# Test_board.net
KiCad netlist of a schematic drawn in EAGLE
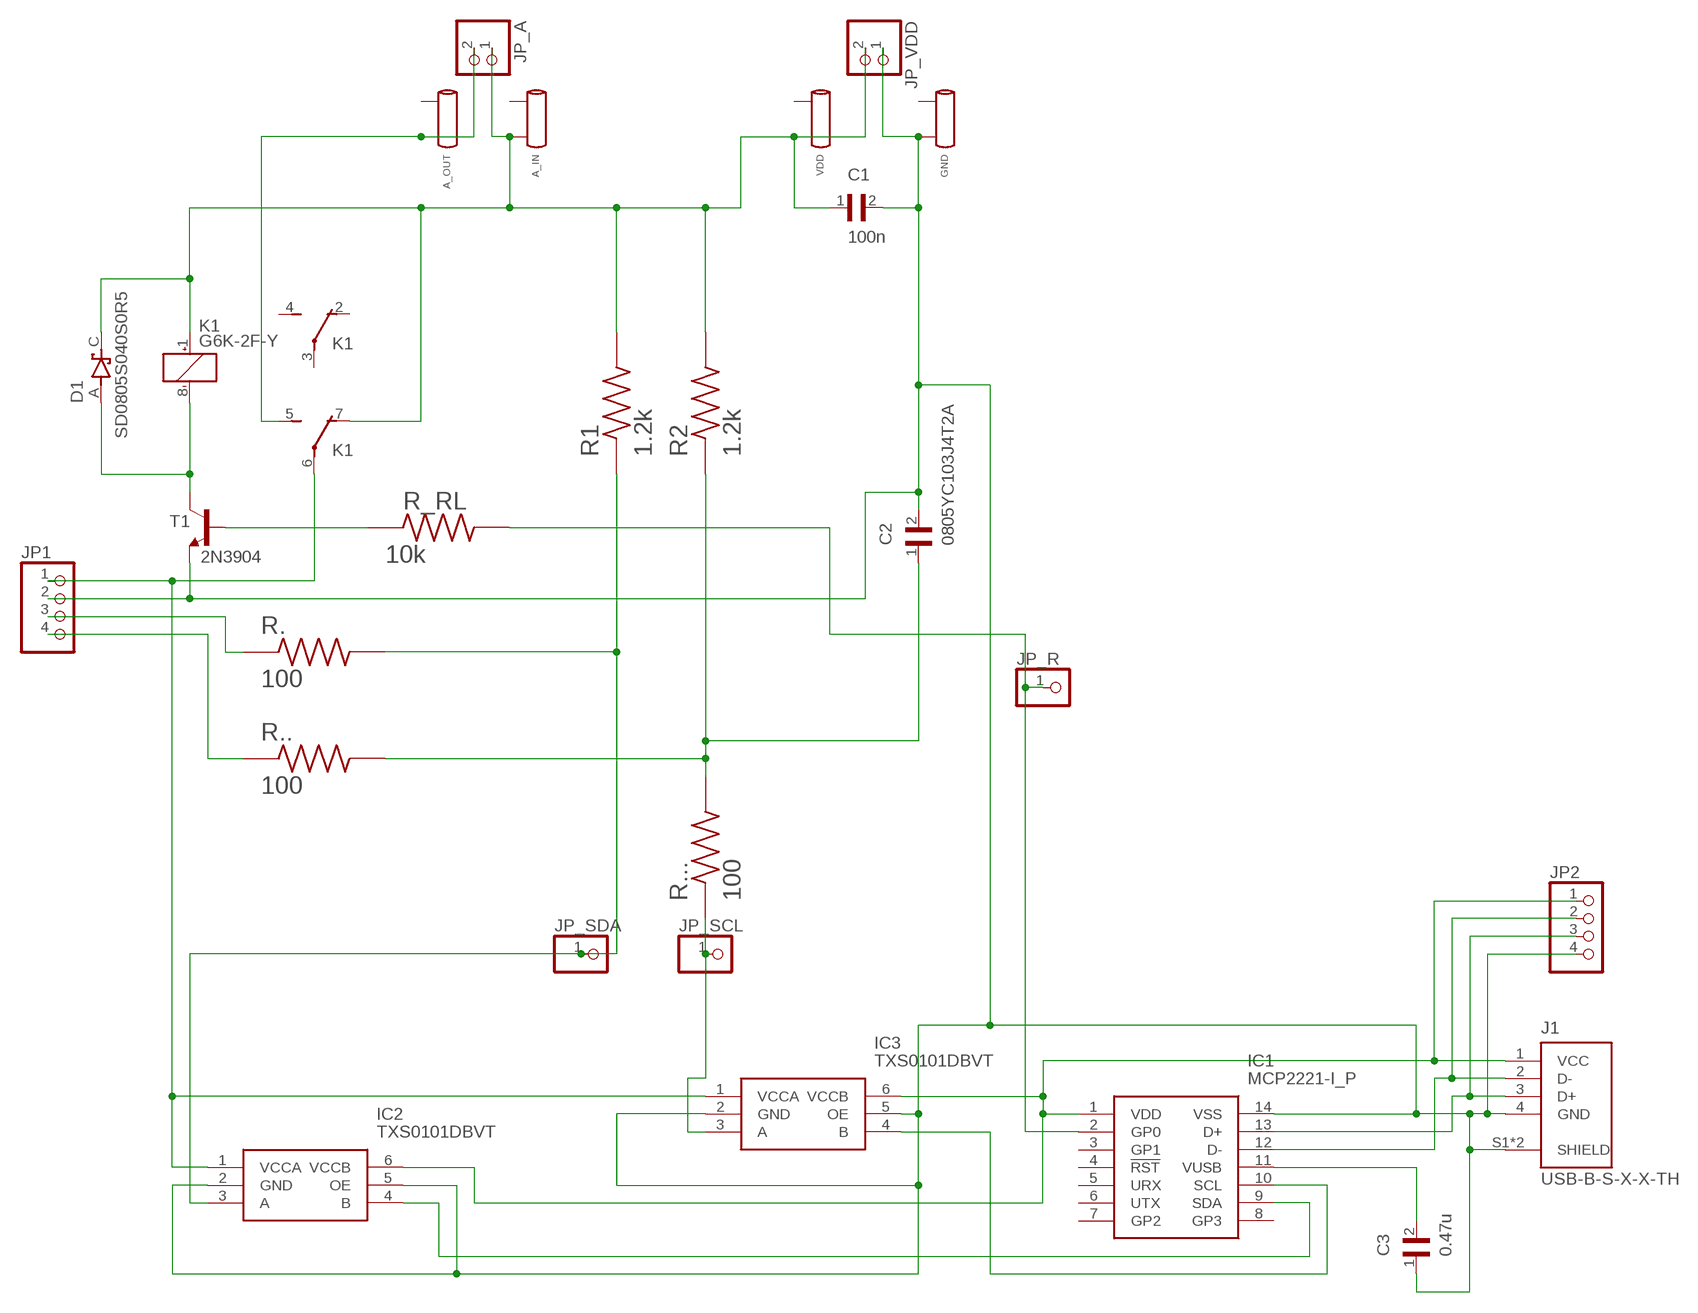
[diagram p0: schematic, sheet 1]

(export (version "E")
  (design (tool "Eeschema 10.0.6"))
  (components
    (comp (ref "A_IN")
      (value "FY_TESTSOCKET")
      (footprint "eagle-import:FY_TESTSOCKET")
      (libsource (lib "eagle-import") (part "FY_TESTSOCKET"))
    )
    (comp (ref "A_OUT")
      (value "FY_TESTSOCKET")
      (footprint "eagle-import:FY_TESTSOCKET")
      (libsource (lib "eagle-import") (part "FY_TESTSOCKET"))
    )
    (comp (ref "C1")
      (value "100n")
      (footprint "eagle-import:CAPC2012X94N")
      (fields (field (name "MF") "AVX") (field (name "MP") "0805YC103J4T2A"))
      (libsource (lib "eagle-import") (part "0805YC103J4T2A"))
    )
    (comp (ref "C2")
      (value "0805YC103J4T2A")
      (footprint "eagle-import:CAPC2012X94N")
      (fields (field (name "MF") "AVX"))
      (libsource (lib "eagle-import") (part "0805YC103J4T2A"))
    )
    (comp (ref "C3")
      (value "0.47u")
      (footprint "eagle-import:CAPC2012X94N")
      (fields (field (name "MF") "AVX") (field (name "MP") "0805YC103J4T2A"))
      (libsource (lib "eagle-import") (part "0805YC103J4T2A"))
    )
    (comp (ref "D1")
      (value "SD0805S040S0R5")
      (footprint "eagle-import:DIOSC130X200X100-2N")
      (fields (field (name "MF") "AVX"))
      (libsource (lib "eagle-import") (part "SD0805S040S0R5"))
    )
    (comp (ref "GND")
      (value "FY_TESTSOCKET")
      (footprint "eagle-import:FY_TESTSOCKET")
      (libsource (lib "eagle-import") (part "FY_TESTSOCKET"))
    )
    (comp (ref "IC1")
      (value "MCP2221-I_P")
      (footprint "eagle-import:DIP781W56P254L1918H533Q14N")
      (fields
        (field (name "ARROW_PART_NUMBER") "MCP2221-I/P")
        (field (name "MOUSER_PART_NUMBER") "579-MCP2221-I/P")
      )
      (libsource (lib "eagle-import") (part "MCP2221-I_P"))
    )
    (comp (ref "IC2")
      (value "TXS0101DBVT")
      (footprint "eagle-import:SOT95P280X145-6N")
      (fields (field (name "MOUSER_PART_NUMBER") "595-TXS0101DBVT"))
      (libsource (lib "eagle-import") (part "TXS0101DBVT"))
    )
    (comp (ref "IC3")
      (value "TXS0101DBVT")
      (footprint "eagle-import:SOT95P280X145-6N")
      (fields (field (name "MOUSER_PART_NUMBER") "595-TXS0101DBVT"))
      (libsource (lib "eagle-import") (part "TXS0101DBVT"))
    )
    (comp (ref "J1")
      (value "USB-B-S-X-X-TH")
      (footprint "eagle-import:SAMTEC_USB-B-S-X-X-TH")
      (fields (field (name "MF") "Samtec") (field (name "MP") "USB-B-S-F-B-TH"))
      (libsource (lib "eagle-import") (part "USB-B-S-X-X-TH"))
    )
    (comp (ref "JP1")
      (value "PINHD-1X4")
      (footprint "eagle-import:1X04")
      (libsource (lib "eagle-import") (part "PINHD-1X4"))
    )
    (comp (ref "JP2")
      (value "PINHD-1X4")
      (footprint "eagle-import:1X04")
      (libsource (lib "eagle-import") (part "PINHD-1X4"))
    )
    (comp (ref "JP_A")
      (value "PINHD-1X2")
      (footprint "eagle-import:1X02")
      (libsource (lib "eagle-import") (part "PINHD-1X2"))
    )
    (comp (ref "JP_R")
      (value "PINHD-1X1")
      (footprint "eagle-import:1X01")
      (libsource (lib "eagle-import") (part "PINHD-1X1"))
    )
    (comp (ref "JP_SCL")
      (value "PINHD-1X1")
      (footprint "eagle-import:1X01")
      (libsource (lib "eagle-import") (part "PINHD-1X1"))
    )
    (comp (ref "JP_SDA")
      (value "PINHD-1X1")
      (footprint "eagle-import:1X01")
      (libsource (lib "eagle-import") (part "PINHD-1X1"))
    )
    (comp (ref "JP_VDD")
      (value "PINHD-1X2")
      (footprint "eagle-import:1X02")
      (libsource (lib "eagle-import") (part "PINHD-1X2"))
    )
    (comp (ref "K1")
      (value "G6K-2F-Y")
      (footprint "eagle-import:G6K-2F-Y")
      (fields (field (name "MF") "OMRON COMPONENTS USA") (field (name "MPN") "G6K-2F-Y DC3"))
      (libsource (lib "eagle-import") (part "G6K-2F-Y"))
    )
    (comp (ref "R.")
      (value "100")
      (footprint "eagle-import:RESC2012X60N")
      (fields (field (name "MF") "Bourns") (field (name "MP") "CR0805AJ/-000EAS"))
      (libsource (lib "eagle-import") (part "CR0805AJ/-000EAS"))
    )
    (comp (ref "R..")
      (value "100")
      (footprint "eagle-import:RESC2012X60N")
      (fields (field (name "MF") "Bourns") (field (name "MP") "CR0805AJ/-000EAS"))
      (libsource (lib "eagle-import") (part "CR0805AJ/-000EAS"))
    )
    (comp (ref "R...")
      (value "100")
      (footprint "eagle-import:RESC2012X60N")
      (fields (field (name "MF") "Bourns") (field (name "MP") "CR0805AJ/-000EAS"))
      (libsource (lib "eagle-import") (part "CR0805AJ/-000EAS"))
    )
    (comp (ref "R1")
      (value "1.2k")
      (footprint "eagle-import:RESC2012X60N")
      (fields (field (name "MF") "Bourns") (field (name "MP") "CR0805AJ/-000EAS"))
      (libsource (lib "eagle-import") (part "CR0805AJ/-000EAS"))
    )
    (comp (ref "R2")
      (value "1.2k")
      (footprint "eagle-import:RESC2012X60N")
      (fields (field (name "MF") "Bourns") (field (name "MP") "CR0805AJ/-000EAS"))
      (libsource (lib "eagle-import") (part "CR0805AJ/-000EAS"))
    )
    (comp (ref "R_RL")
      (value "10k")
      (footprint "eagle-import:RESC2012X60N")
      (fields (field (name "MF") "Bourns") (field (name "MP") "CR0805AJ/-000EAS"))
      (libsource (lib "eagle-import") (part "CR0805AJ/-000EAS"))
    )
    (comp (ref "T1")
      (value "2N3904")
      (footprint "eagle-import:TO92")
      (libsource (lib "eagle-import") (part "2N3904"))
    )
    (comp (ref "VDD")
      (value "FY_TESTSOCKET")
      (footprint "eagle-import:FY_TESTSOCKET")
      (libsource (lib "eagle-import") (part "FY_TESTSOCKET"))
    )
  )
  (nets
    (net (code "1") (name "Net-(C2-Pad1)") (class "Default")
      (node (ref "C2") (pin "1") (pinfunction "1_1") (pintype "passive"))
      (node (ref "R..") (pin "2") (pinfunction "2_2") (pintype "passive"))
      (node (ref "R...") (pin "2") (pinfunction "2_2") (pintype "passive"))
      (node (ref "R2") (pin "1") (pinfunction "1_1") (pintype "passive"))
    )
    (net (code "2") (name "Net-(D1-K)") (class "Default")
      (node (ref "A_IN") (pin "P$2") (pinfunction "P$2_P$2") (pintype "bidirectional"))
      (node (ref "C1") (pin "1") (pinfunction "1_1") (pintype "passive"))
      (node (ref "D1") (pin "C") (pinfunction "K_C") (pintype "passive"))
      (node (ref "JP_A") (pin "1") (pinfunction "1_1") (pintype "passive"))
      (node (ref "JP_VDD") (pin "2") (pinfunction "2_2") (pintype "passive"))
      (node (ref "K1") (pin "1") (pinfunction "+_1") (pintype "passive"))
      (node (ref "K1") (pin "7") (pinfunction "O_7") (pintype "passive"))
      (node (ref "R1") (pin "2") (pinfunction "2_2") (pintype "passive"))
      (node (ref "R2") (pin "2") (pinfunction "2_2") (pintype "passive"))
      (node (ref "VDD") (pin "P$2") (pinfunction "P$2_P$2") (pintype "bidirectional"))
    )
    (net (code "3") (name "Net-(IC1-D+)") (class "Default")
      (node (ref "IC1") (pin "13") (pinfunction "D+_13") (pintype "bidirectional"))
      (node (ref "J1") (pin "3") (pinfunction "D+_3") (pintype "bidirectional"))
      (node (ref "JP2") (pin "3") (pinfunction "3_3") (pintype "passive"))
    )
    (net (code "4") (name "Net-(IC1-D-)") (class "Default")
      (node (ref "IC1") (pin "12") (pinfunction "D-_12") (pintype "bidirectional"))
      (node (ref "J1") (pin "2") (pinfunction "D-_2") (pintype "bidirectional"))
      (node (ref "JP2") (pin "2") (pinfunction "2_2") (pintype "passive"))
    )
    (net (code "5") (name "Net-(IC1-GP0)") (class "Default")
      (node (ref "IC1") (pin "2") (pinfunction "GP0_2") (pintype "bidirectional"))
      (node (ref "JP_R") (pin "1") (pinfunction "1_1") (pintype "passive"))
      (node (ref "R_RL") (pin "2") (pinfunction "2_2") (pintype "passive"))
    )
    (net (code "6") (name "Net-(IC1-SCL)") (class "Default")
      (node (ref "IC1") (pin "10") (pinfunction "SCL_10") (pintype "bidirectional"))
      (node (ref "IC3") (pin "4") (pinfunction "B_4") (pintype "bidirectional"))
    )
    (net (code "7") (name "Net-(IC1-SDA)") (class "Default")
      (node (ref "IC1") (pin "9") (pinfunction "SDA_9") (pintype "bidirectional"))
      (node (ref "IC2") (pin "4") (pinfunction "B_4") (pintype "bidirectional"))
    )
    (net (code "8") (name "Net-(IC1-VDD)") (class "Default")
      (node (ref "IC1") (pin "1") (pinfunction "VDD_1") (pintype "bidirectional"))
      (node (ref "IC2") (pin "6") (pinfunction "VCCB_6") (pintype "bidirectional"))
      (node (ref "IC3") (pin "6") (pinfunction "VCCB_6") (pintype "bidirectional"))
      (node (ref "J1") (pin "1") (pinfunction "VCC_1") (pintype "power_in"))
      (node (ref "JP2") (pin "1") (pinfunction "1_1") (pintype "passive"))
    )
    (net (code "9") (name "Net-(IC1-VSS)") (class "Default")
      (node (ref "C1") (pin "2") (pinfunction "2_2") (pintype "passive"))
      (node (ref "C2") (pin "2") (pinfunction "2_2") (pintype "passive"))
      (node (ref "C3") (pin "1") (pinfunction "1_1") (pintype "passive"))
      (node (ref "GND") (pin "P$2") (pinfunction "P$2_P$2") (pintype "bidirectional"))
      (node (ref "IC1") (pin "14") (pinfunction "VSS_14") (pintype "bidirectional"))
      (node (ref "IC2") (pin "2") (pinfunction "GND_2") (pintype "bidirectional"))
      (node (ref "IC2") (pin "5") (pinfunction "OE_5") (pintype "bidirectional"))
      (node (ref "IC3") (pin "2") (pinfunction "GND_2") (pintype "bidirectional"))
      (node (ref "IC3") (pin "5") (pinfunction "OE_5") (pintype "bidirectional"))
      (node (ref "J1") (pin "4") (pinfunction "GND_4") (pintype "power_in"))
      (node (ref "J1") (pin "S1") (pinfunction "SHIELD_S1") (pintype "passive"))
      (node (ref "J1") (pin "S2") (pinfunction "SHIELD_S2") (pintype "passive"))
      (node (ref "JP1") (pin "2") (pinfunction "2_2") (pintype "passive"))
      (node (ref "JP2") (pin "4") (pinfunction "4_4") (pintype "passive"))
      (node (ref "JP_VDD") (pin "1") (pinfunction "1_1") (pintype "passive"))
      (node (ref "T1") (pin "3") (pinfunction "E_3") (pintype "passive"))
    )
    (net (code "10") (name "Net-(IC1-VUSB)") (class "Default")
      (node (ref "C3") (pin "2") (pinfunction "2_2") (pintype "passive"))
      (node (ref "IC1") (pin "11") (pinfunction "VUSB_11") (pintype "bidirectional"))
    )
    (net (code "11") (name "Net-(IC2-A)") (class "Default")
      (node (ref "IC2") (pin "3") (pinfunction "A_3") (pintype "bidirectional"))
      (node (ref "JP_SDA") (pin "1") (pinfunction "1_1") (pintype "passive"))
      (node (ref "R.") (pin "2") (pinfunction "2_2") (pintype "passive"))
      (node (ref "R1") (pin "1") (pinfunction "1_1") (pintype "passive"))
    )
    (net (code "12") (name "Net-(IC2-VCCA)") (class "Default")
      (node (ref "IC2") (pin "1") (pinfunction "VCCA_1") (pintype "bidirectional"))
      (node (ref "IC3") (pin "1") (pinfunction "VCCA_1") (pintype "bidirectional"))
      (node (ref "JP1") (pin "1") (pinfunction "1_1") (pintype "passive"))
      (node (ref "K1") (pin "6") (pinfunction "P_6") (pintype "passive"))
    )
    (net (code "13") (name "Net-(IC3-A)") (class "Default")
      (node (ref "IC3") (pin "3") (pinfunction "A_3") (pintype "bidirectional"))
      (node (ref "JP_SCL") (pin "1") (pinfunction "1_1") (pintype "passive"))
      (node (ref "R...") (pin "1") (pinfunction "1_1") (pintype "passive"))
    )
    (net (code "14") (name "Net-(JP1-Pad3)") (class "Default")
      (node (ref "JP1") (pin "3") (pinfunction "3_3") (pintype "passive"))
      (node (ref "R.") (pin "1") (pinfunction "1_1") (pintype "passive"))
    )
    (net (code "15") (name "Net-(JP1-Pad4)") (class "Default")
      (node (ref "JP1") (pin "4") (pinfunction "4_4") (pintype "passive"))
      (node (ref "R..") (pin "1") (pinfunction "1_1") (pintype "passive"))
    )
    (net (code "16") (name "Net-(K1A--)") (class "Default")
      (node (ref "D1") (pin "A") (pinfunction "A_A") (pintype "passive"))
      (node (ref "K1") (pin "8") (pinfunction "-_8") (pintype "passive"))
      (node (ref "T1") (pin "1") (pinfunction "C_1") (pintype "passive"))
    )
    (net (code "17") (name "Net-(K1C-S)") (class "Default")
      (node (ref "A_OUT") (pin "P$2") (pinfunction "P$2_P$2") (pintype "bidirectional"))
      (node (ref "JP_A") (pin "2") (pinfunction "2_2") (pintype "passive"))
      (node (ref "K1") (pin "5") (pinfunction "S_5") (pintype "passive"))
    )
    (net (code "18") (name "Net-(T1-B)") (class "Default")
      (node (ref "R_RL") (pin "1") (pinfunction "1_1") (pintype "passive"))
      (node (ref "T1") (pin "2") (pinfunction "B_2") (pintype "passive"))
    )
    (net (code "19") (name "unconnected-(A_IN-PadP$1)") (class "Default")
      (node (ref "A_IN") (pin "P$1") (pinfunction "P$1_P$1") (pintype "bidirectional"))
    )
    (net (code "20") (name "unconnected-(A_OUT-PadP$1)") (class "Default")
      (node (ref "A_OUT") (pin "P$1") (pinfunction "P$1_P$1") (pintype "bidirectional"))
    )
    (net (code "21") (name "unconnected-(GND-PadP$1)") (class "Default")
      (node (ref "GND") (pin "P$1") (pinfunction "P$1_P$1") (pintype "bidirectional"))
    )
    (net (code "22") (name "unconnected-(IC1-GP1-Pad3)") (class "Default")
      (node (ref "IC1") (pin "3") (pinfunction "GP1_3") (pintype "bidirectional"))
    )
    (net (code "23") (name "unconnected-(IC1-GP2-Pad7)") (class "Default")
      (node (ref "IC1") (pin "7") (pinfunction "GP2_7") (pintype "bidirectional"))
    )
    (net (code "24") (name "unconnected-(IC1-GP3-Pad8)") (class "Default")
      (node (ref "IC1") (pin "8") (pinfunction "GP3_8") (pintype "bidirectional"))
    )
    (net (code "25") (name "unconnected-(IC1-URX-Pad5)") (class "Default")
      (node (ref "IC1") (pin "5") (pinfunction "URX_5") (pintype "bidirectional"))
    )
    (net (code "26") (name "unconnected-(IC1-UTX-Pad6)") (class "Default")
      (node (ref "IC1") (pin "6") (pinfunction "UTX_6") (pintype "bidirectional"))
    )
    (net (code "27") (name "unconnected-(IC1-~{RST}-Pad4)") (class "Default")
      (node (ref "IC1") (pin "4") (pinfunction "~{RST}_4") (pintype "bidirectional"))
    )
    (net (code "28") (name "unconnected-(K1B-O-Pad2)") (class "Default")
      (node (ref "K1") (pin "2") (pinfunction "O_2") (pintype "passive"))
    )
    (net (code "29") (name "unconnected-(K1B-P-Pad3)") (class "Default")
      (node (ref "K1") (pin "3") (pinfunction "P_3") (pintype "passive"))
    )
    (net (code "30") (name "unconnected-(K1B-S-Pad4)") (class "Default")
      (node (ref "K1") (pin "4") (pinfunction "S_4") (pintype "passive"))
    )
    (net (code "31") (name "unconnected-(VDD-PadP$1)") (class "Default")
      (node (ref "VDD") (pin "P$1") (pinfunction "P$1_P$1") (pintype "bidirectional"))
    )
  )
)
